# GSR.net
KiCad netlist of a schematic drawn in Altium Designer
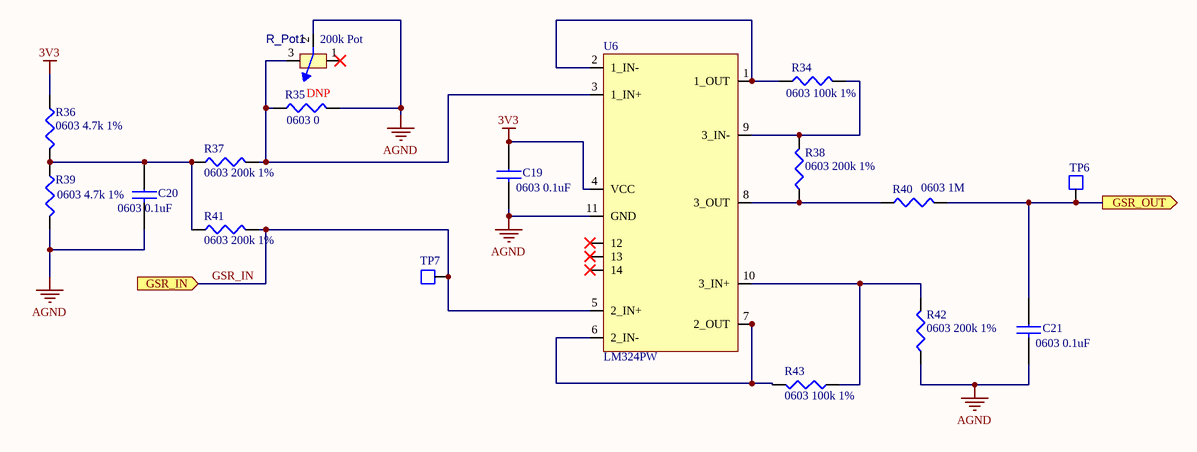
[diagram p0: GSR.SchDoc]

(export (version "E")
  (design (tool "Eeschema 10.0.6"))
  (components
    (comp (ref "C19")
      (value "0603 0.1uF")
      (footprint "CAP_0603_CER")
      (description "Generic Cap for NC (No Polar)\r\nESR <30mOhm\r\nESL <1.5nH,\r\nX7R")
      (fields
        (field (name "MANUFACTURER") "KEMET")
        (field (name "MANUFACTURER PART NUMBER") "C0603C104K5RAC7867")
      )
      (libsource (lib "BioSens") (part "CAP_NP"))
    )
    (comp (ref "C20")
      (value "0603 0.1uF")
      (footprint "CAP_0603_CER")
      (description "Generic Cap for NC (No Polar)\r\nESR <30mOhm\r\nESL <1.5nH,\r\nX7R")
      (fields
        (field (name "MANUFACTURER") "KEMET")
        (field (name "MANUFACTURER PART NUMBER") "C0603C104K5RAC7867")
      )
      (libsource (lib "BioSens") (part "CAP_NP"))
    )
    (comp (ref "C21")
      (value "0603 0.1uF")
      (footprint "CAP_0603_CER")
      (description "Generic Cap for NC (No Polar)\r\nESR <30mOhm\r\nESL <1.5nH,\r\nX7R or X5R")
      (fields
        (field (name "MANUFACTURER") "KEMET")
        (field (name "MANUFACTURER PART NUMBER") "C0603C104K5RAC7867")
      )
      (libsource (lib "BioSens") (part "CAP_NP"))
    )
    (comp (ref "R34")
      (value "0603 100k 1%")
      (footprint "0603")
      (description "Generic Resistor")
      (fields
        (field (name "MANUFACTURER PART NUMBER") "CRCW0402100KFKEDC")
        (field (name "MANUFACTURER") "Vishay Dale")
      )
      (libsource (lib "BioSens") (part "RESISTOR"))
    )
    (comp (ref "R35")
      (value "0603 0")
      (footprint "0603")
      (description "Generic Resistor")
      (fields
        (field (name "MANUFACTURER PART NUMBER") "RC0402FR-070RL")
        (field (name "MANUFACTURER") "YAGEO")
      )
      (libsource (lib "BioSens") (part "RESISTOR"))
    )
    (comp (ref "R36")
      (value "0603 4.7k 1%")
      (footprint "0603")
      (description "Generic Resistor")
      (fields
        (field (name "MANUFACTURER PART NUMBER") "RC0402FR-074K7L")
        (field (name "MANUFACTURER") "YAGEO")
      )
      (libsource (lib "BioSens") (part "RESISTOR"))
    )
    (comp (ref "R37")
      (value "0603 200k 1%")
      (footprint "0603")
      (description "Generic Resistor")
      (fields
        (field (name "MANUFACTURER PART NUMBER") "RC0402FR-13200KL")
        (field (name "MANUFACTURER") "YAGEO")
      )
      (libsource (lib "BioSens") (part "RESISTOR"))
    )
    (comp (ref "R38")
      (value "0603 200k 1%")
      (footprint "0603")
      (description "Generic Resistor")
      (fields
        (field (name "MANUFACTURER PART NUMBER") "RC0402FR-13200KL")
        (field (name "MANUFACTURER") "YAGEO")
      )
      (libsource (lib "BioSens") (part "RESISTOR"))
    )
    (comp (ref "R39")
      (value "0603 4.7k 1%")
      (footprint "0603")
      (description "Generic Resistor")
      (fields
        (field (name "MANUFACTURER PART NUMBER") "RC0402FR-074K7L")
        (field (name "MANUFACTURER") "YAGEO")
      )
      (libsource (lib "BioSens") (part "RESISTOR"))
    )
    (comp (ref "R40")
      (value "0603 1M")
      (footprint "0603")
      (description "Generic Resistor")
      (fields
        (field (name "MANUFACTURER PART NUMBER") "RC0402FR-071ML")
        (field (name "MANUFACTURER") "YAGEO")
      )
      (libsource (lib "BioSens") (part "RESISTOR"))
    )
    (comp (ref "R41")
      (value "0603 200k 1%")
      (footprint "0603")
      (description "Generic Resistor")
      (fields
        (field (name "MANUFACTURER PART NUMBER") "RC0402FR-13200KL")
        (field (name "MANUFACTURER") "YAGEO")
      )
      (libsource (lib "BioSens") (part "RESISTOR"))
    )
    (comp (ref "R42")
      (value "0603 200k 1%")
      (footprint "0603")
      (description "Generic Resistor")
      (fields
        (field (name "MANUFACTURER PART NUMBER") "RC0402FR-13200KL")
        (field (name "MANUFACTURER") "YAGEO")
      )
      (libsource (lib "BioSens") (part "RESISTOR"))
    )
    (comp (ref "R43")
      (value "0603 100k 1%")
      (footprint "0603")
      (description "Generic Resistor")
      (fields
        (field (name "MANUFACTURER PART NUMBER") "CRCW0402100KFKEDC")
        (field (name "MANUFACTURER") "Vishay Dale")
      )
      (libsource (lib "BioSens") (part "RESISTOR"))
    )
    (comp (ref "R_Pot1")
      (value "200k Pot")
      (footprint "R_200k_Pot")
      (description "SMD Single-Turn Trimmer Potentiometers 1/4 SQ 200KOHMS 10% 0.5WATTS")
      (fields
        (field (name "MANUFACTURER") "Bourns")
        (field (name "MANUFACTURER PART NUMBER") "3361P-1-204GLF")
      )
      (libsource (lib "BioSens") (part "R200k_Pot"))
    )
    (comp (ref "TP6")
      (value "0402_TEST_PT")
      (footprint "0402_PAD")
      (libsource (lib "BioSens") (part "0402_TEST_PT"))
    )
    (comp (ref "TP7")
      (value "0402_TEST_PT")
      (footprint "0402_PAD")
      (libsource (lib "BioSens") (part "0402_TEST_PT"))
    )
    (comp (ref "U6")
      (value "LM324PW")
      (footprint "TSOP65P640X120-14N")
      (description "Integrated Circuit Operational Amplifier LM324/TSSOP/LM324PW TEXAS INSTRUMENT RoHS TSSOP14")
      (fields (field (name "MANUFACTURER") "Texas Instruments"))
      (libsource (lib "BioSens") (part "LM324PW"))
    )
  )
  (nets
    (net (code "1") (name "/GSR_IN") (class "Default")
      (node (ref "R41") (pin "2") (pinfunction "2_2") (pintype "passive"))
      (node (ref "TP7") (pin "1") (pintype "passive"))
      (node (ref "U6") (pin "5") (pinfunction "2_IN+_5") (pintype "passive"))
    )
    (net (code "2") (name "/GSR_OUT") (class "Default")
      (node (ref "C21") (pin "1") (pinfunction "1_1") (pintype "passive"))
      (node (ref "R40") (pin "2") (pinfunction "2_2") (pintype "passive"))
      (node (ref "TP6") (pin "1") (pintype "passive"))
    )
    (net (code "3") (name "3V3") (class "Default")
      (node (ref "C19") (pin "1") (pinfunction "1_1") (pintype "passive"))
      (node (ref "R36") (pin "1") (pinfunction "1_1") (pintype "passive"))
      (node (ref "U6") (pin "4") (pinfunction "VCC_4") (pintype "passive"))
    )
    (net (code "4") (name "AGND") (class "Default")
      (node (ref "C19") (pin "2") (pinfunction "2_2") (pintype "passive"))
      (node (ref "C20") (pin "2") (pinfunction "2_2") (pintype "passive"))
      (node (ref "C21") (pin "2") (pinfunction "2_2") (pintype "passive"))
      (node (ref "R35") (pin "2") (pinfunction "2_2") (pintype "passive"))
      (node (ref "R39") (pin "2") (pinfunction "2_2") (pintype "passive"))
      (node (ref "R42") (pin "1") (pinfunction "1_1") (pintype "passive"))
      (node (ref "R_Pot1") (pin "2") (pinfunction "2_2") (pintype "passive"))
      (node (ref "U6") (pin "11") (pinfunction "GND_11") (pintype "passive"))
    )
    (net (code "5") (name "Net-(C20-Pad1)") (class "Default")
      (node (ref "C20") (pin "1") (pinfunction "1_1") (pintype "passive"))
      (node (ref "R36") (pin "2") (pinfunction "2_2") (pintype "passive"))
      (node (ref "R37") (pin "1") (pinfunction "1_1") (pintype "passive"))
      (node (ref "R39") (pin "1") (pinfunction "1_1") (pintype "passive"))
      (node (ref "R41") (pin "1") (pinfunction "1_1") (pintype "passive"))
    )
    (net (code "6") (name "Net-(U6-1_IN+)") (class "Default")
      (node (ref "R35") (pin "1") (pinfunction "1_1") (pintype "passive"))
      (node (ref "R37") (pin "2") (pinfunction "2_2") (pintype "passive"))
      (node (ref "R_Pot1") (pin "3") (pinfunction "3_3") (pintype "passive"))
      (node (ref "U6") (pin "3") (pinfunction "1_IN+_3") (pintype "passive"))
    )
    (net (code "7") (name "Net-(U6-1_IN-)") (class "Default")
      (node (ref "R34") (pin "1") (pinfunction "1_1") (pintype "passive"))
      (node (ref "U6") (pin "1") (pinfunction "1_OUT_1") (pintype "passive"))
      (node (ref "U6") (pin "2") (pinfunction "1_IN-_2") (pintype "passive"))
    )
    (net (code "8") (name "Net-(U6-2_IN-)") (class "Default")
      (node (ref "R43") (pin "2") (pinfunction "2_2") (pintype "passive"))
      (node (ref "U6") (pin "6") (pinfunction "2_IN-_6") (pintype "passive"))
      (node (ref "U6") (pin "7") (pinfunction "2_OUT_7") (pintype "passive"))
    )
    (net (code "9") (name "Net-(U6-3_IN+)") (class "Default")
      (node (ref "R42") (pin "2") (pinfunction "2_2") (pintype "passive"))
      (node (ref "R43") (pin "1") (pinfunction "1_1") (pintype "passive"))
      (node (ref "U6") (pin "10") (pinfunction "3_IN+_10") (pintype "passive"))
    )
    (net (code "10") (name "Net-(U6-3_IN-)") (class "Default")
      (node (ref "R34") (pin "2") (pinfunction "2_2") (pintype "passive"))
      (node (ref "R38") (pin "2") (pinfunction "2_2") (pintype "passive"))
      (node (ref "U6") (pin "9") (pinfunction "3_IN-_9") (pintype "passive"))
    )
    (net (code "11") (name "Net-(U6-3_OUT)") (class "Default")
      (node (ref "R38") (pin "1") (pinfunction "1_1") (pintype "passive"))
      (node (ref "R40") (pin "1") (pinfunction "1_1") (pintype "passive"))
      (node (ref "U6") (pin "8") (pinfunction "3_OUT_8") (pintype "passive"))
    )
    (net (code "12") (name "unconnected-(R_Pot1-Pad1)") (class "Default")
      (node (ref "R_Pot1") (pin "1") (pinfunction "1_1") (pintype "passive+no_connect"))
    )
    (net (code "13") (name "unconnected-(U6-Pad12)") (class "Default")
      (node (ref "U6") (pin "12") (pinfunction "12_12") (pintype "passive+no_connect"))
    )
    (net (code "14") (name "unconnected-(U6-Pad13)") (class "Default")
      (node (ref "U6") (pin "13") (pinfunction "13_13") (pintype "passive+no_connect"))
    )
    (net (code "15") (name "unconnected-(U6-Pad14)") (class "Default")
      (node (ref "U6") (pin "14") (pinfunction "14_14") (pintype "passive+no_connect"))
    )
  )
)
